# receiver.net
KiCad netlist of a schematic drawn in EAGLE
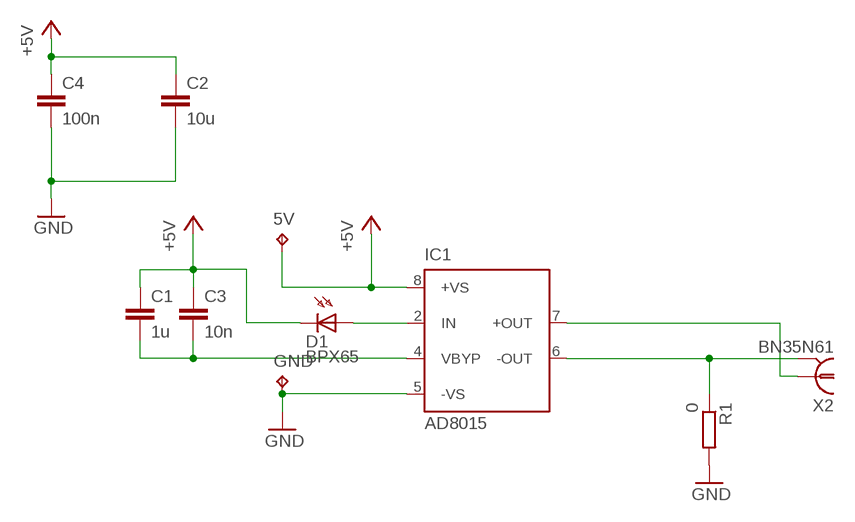
[diagram p0: schematic, sheet 1]

(export (version "E")
  (design (tool "Eeschema 10.0.6"))
  (components
    (comp (ref "5V")
      (value "TPTP20SQ")
      (footprint "eagle-import:TP20SQ")
      (libsource (lib "eagle-import") (part "TPTP20SQ"))
    )
    (comp (ref "C1")
      (value "1u")
      (footprint "eagle-import:C1206")
      (libsource (lib "eagle-import") (part "C-EUC1206"))
    )
    (comp (ref "C2")
      (value "10u")
      (footprint "eagle-import:C1206")
      (libsource (lib "eagle-import") (part "C-EUC1206"))
    )
    (comp (ref "C3")
      (value "10n")
      (footprint "eagle-import:C0603")
      (libsource (lib "eagle-import") (part "C-EUC0603"))
    )
    (comp (ref "C4")
      (value "100n")
      (footprint "eagle-import:C0603")
      (libsource (lib "eagle-import") (part "C-EUC0603"))
    )
    (comp (ref "D1")
      (value "BPX65")
      (footprint "eagle-import:BPX65")
      (fields (field (name "MPN") "BPX65."))
      (libsource (lib "eagle-import") (part "BPX65"))
    )
    (comp (ref "GND")
      (value "TPTP20SQ")
      (footprint "eagle-import:TP20SQ")
      (libsource (lib "eagle-import") (part "TPTP20SQ"))
    )
    (comp (ref "IC1")
      (value "AD8015")
      (footprint "eagle-import:SO8")
      (fields (field (name "MPN") "AD8015ARZ"))
      (libsource (lib "eagle-import") (part "AD8015"))
    )
    (comp (ref "R1")
      (value "0")
      (footprint "eagle-import:R1206")
      (libsource (lib "eagle-import") (part "R-EU_R1206"))
    )
    (comp (ref "X2")
      (value "BN35N61")
      (footprint "eagle-import:B35N61")
      (libsource (lib "eagle-import") (part "BN35N61"))
    )
  )
  (nets
    (net (code "1") (name "+5V") (class "Default")
      (node (ref "5V") (pin "TP") (pinfunction "TP_TP") (pintype "input"))
      (node (ref "C1") (pin "1") (pinfunction "1_1") (pintype "passive"))
      (node (ref "C2") (pin "1") (pinfunction "1_1") (pintype "passive"))
      (node (ref "C3") (pin "1") (pinfunction "1_1") (pintype "passive"))
      (node (ref "C4") (pin "1") (pinfunction "1_1") (pintype "passive"))
      (node (ref "D1") (pin "K") (pinfunction "C_K") (pintype "passive"))
      (node (ref "IC1") (pin "8") (pinfunction "+VS_8") (pintype "input"))
    )
    (net (code "2") (name "GND") (class "Default")
      (node (ref "C2") (pin "2") (pinfunction "2_2") (pintype "passive"))
      (node (ref "C4") (pin "2") (pinfunction "2_2") (pintype "passive"))
      (node (ref "GND") (pin "TP") (pinfunction "TP_TP") (pintype "input"))
      (node (ref "IC1") (pin "5") (pinfunction "-VS_5") (pintype "input"))
      (node (ref "R1") (pin "2") (pinfunction "2_2") (pintype "passive"))
    )
    (net (code "3") (name "Net-(IC1-+OUT)") (class "Default")
      (node (ref "IC1") (pin "7") (pinfunction "+OUT_7") (pintype "output"))
      (node (ref "X2") (pin "1") (pinfunction "1_1") (pintype "passive"))
    )
    (net (code "4") (name "Net-(IC1--OUT)") (class "Default")
      (node (ref "IC1") (pin "6") (pinfunction "-OUT_6") (pintype "output"))
      (node (ref "R1") (pin "1") (pinfunction "1_1") (pintype "passive"))
      (node (ref "X2") (pin "2") (pinfunction "2_2") (pintype "passive"))
      (node (ref "X2") (pin "3") (pinfunction "2_3") (pintype "passive"))
      (node (ref "X2") (pin "4") (pinfunction "2_4") (pintype "passive"))
      (node (ref "X2") (pin "5") (pinfunction "2_5") (pintype "passive"))
    )
    (net (code "5") (name "Net-(IC1-IN)") (class "Default")
      (node (ref "D1") (pin "A") (pinfunction "A_A") (pintype "passive"))
      (node (ref "IC1") (pin "2") (pinfunction "IN_2") (pintype "input"))
    )
    (net (code "6") (name "Net-(IC1-VBYP)") (class "Default")
      (node (ref "C1") (pin "2") (pinfunction "2_2") (pintype "passive"))
      (node (ref "C3") (pin "2") (pinfunction "2_2") (pintype "passive"))
      (node (ref "IC1") (pin "4") (pinfunction "VBYP_4") (pintype "input"))
    )
  )
)
